# RS485.net
KiCad netlist of a schematic drawn in Altium Designer
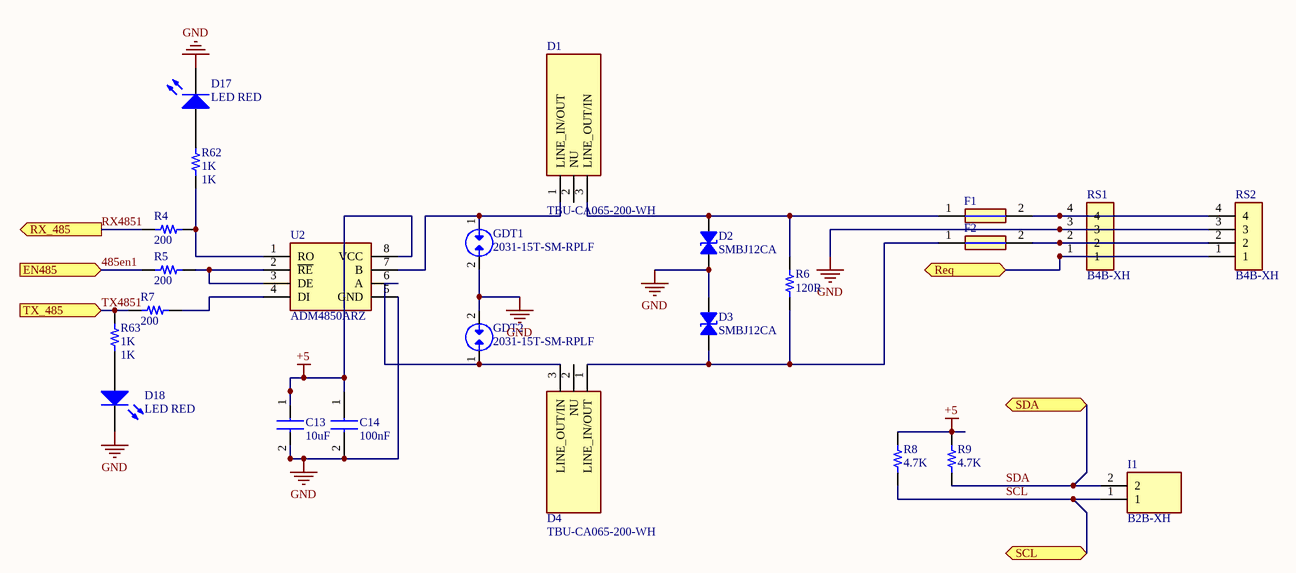
[diagram p0: RS485.SchDoc]

(export (version "E")
  (design (tool "Eeschema 10.0.6"))
  (components
    (comp (ref "C13")
      (value "10uF")
      (footprint "0603C")
      (description "CAP SMD 0603")
      (fields
        (field (name "MANUFACTURER_PART_NUMBER") "C1206C104Z5UACTU")
        (field (name "MOUSER PART NUMBER") "80-C1206C104Z5U")
      )
      (libsource (lib "*") (part "C1206C104Z5UACTU"))
    )
    (comp (ref "C14")
      (value "100nF")
      (footprint "0603C")
      (description "CAP SMD 0603")
      (fields
        (field (name "MANUFACTURER_PART_NUMBER") "C1206C104Z5UACTU")
        (field (name "MOUSER PART NUMBER") "80-C1206C104Z5U")
      )
      (libsource (lib "*") (part "C1206C104Z5UACTU"))
    )
    (comp (ref "D1")
      (value "TBU-CA065-200-WH")
      (footprint "TBUCA025050WH")
      (description "TVS Diode (Bi-directional)")
      (fields (field (name "MOUSER PART NUMBER") "652-TBU-CA065-200-WH"))
      (libsource (lib "*") (part "TBU-CA065-200-WH"))
    )
    (comp (ref "D2")
      (value "SMBJ12CA")
      (footprint "DO214AA SMB")
      (description "TVS DIODE 12V 19.9V SMB")
      (fields (field (name "MANUFACTURER") "AVX Corporation"))
      (libsource (lib "Celestial Altium Library - altium_library") (part "Diode TVS"))
    )
    (comp (ref "D3")
      (value "SMBJ12CA")
      (footprint "DO214AA SMB")
      (description "TVS DIODE 12V 19.9V SMB")
      (fields (field (name "MANUFACTURER") "AVX Corporation"))
      (libsource (lib "Celestial Altium Library - altium_library") (part "Diode TVS"))
    )
    (comp (ref "D4")
      (value "TBU-CA065-200-WH")
      (footprint "TBUCA025050WH")
      (description "TVS Diode (Bi-directional)")
      (fields (field (name "MOUSER PART NUMBER") "652-TBU-CA065-200-WH"))
      (libsource (lib "") (part "TBU-CA065-200-WH_1"))
    )
    (comp (ref "D17")
      (value "LED RED")
      (footprint "LED_0805 G")
      (description "LED SMD 0805 RED")
      (fields (field (name "PUBLISHER") "Altium Limited"))
      (libsource (lib "Miscellaneous Devices") (part "LED0"))
    )
    (comp (ref "D18")
      (value "LED RED")
      (footprint "LED_0805 G")
      (description "LED SMD 0805 RED")
      (fields (field (name "PUBLISHER") "Altium Limited"))
      (libsource (lib "Miscellaneous Devices") (part "LED0"))
    )
    (comp (ref "F1")
      (value "fuse 100mAmp")
      (footprint "1206 FUSE")
      (description "Fuse 1206")
      (fields (field (name "MANUFACTURER_PART_NUMBER") "1206SFS200F/63-2"))
      (libsource (lib "*") (part "1206SFS200F_63-2"))
    )
    (comp (ref "F2")
      (value "fuse 100mAmp")
      (footprint "1206 FUSE")
      (description "Fuse 1206")
      (fields (field (name "MANUFACTURER_PART_NUMBER") "1206SFS200F/63-2"))
      (libsource (lib "*") (part "1206SFS200F_63-2"))
    )
    (comp (ref "GDT1")
      (value "2031-15T-SM-RPLF")
      (footprint "TVS_2031-15T-SM-RPLF")
      (description "Gas Discharge Tube SMD")
      (libsource (lib "2031-15T-SM-RPLF") (part "2031-15T-SM-RPLF"))
    )
    (comp (ref "GDT2")
      (value "2031-15T-SM-RPLF")
      (footprint "TVS_2031-15T-SM-RPLF")
      (description "Gas Discharge Tube SMD")
      (libsource (lib "2031-15T-SM-RPLF") (part "2031-15T-SM-RPLF"))
    )
    (comp (ref "I1")
      (value "B2B-XH")
      (footprint "JST-B2B-XH")
      (description "XH 2pin standing")
      (libsource (lib "XHBBLIB") (part "B2B-XH"))
    )
    (comp (ref "R4")
      (value "200")
      (footprint "0603R")
      (description "RES SMD 0603")
      (fields (field (name "PART NUMBER") "CRCW080510K0JNEAIF") (field (name "MANUFACTURER") "Vishay Dale"))
      (libsource (lib "Celestial Altium Library - altium_library") (part "Resistor"))
    )
    (comp (ref "R5")
      (value "200")
      (footprint "0603R")
      (description "RES SMD 0603")
      (fields (field (name "PART NUMBER") "CRCW080510K0JNEAIF") (field (name "MANUFACTURER") "Vishay Dale"))
      (libsource (lib "Celestial Altium Library - altium_library") (part "Resistor"))
    )
    (comp (ref "R6")
      (value "120R")
      (footprint "0603R")
      (description "RES SMD 0603")
      (fields (field (name "PART NUMBER") "CRCW080510K0JNEAIF") (field (name "MANUFACTURER") "Vishay Dale"))
      (libsource (lib "Celestial Altium Library - altium_library") (part "Resistor"))
    )
    (comp (ref "R7")
      (value "200")
      (footprint "0603R")
      (description "RES SMD 0603")
      (fields (field (name "PART NUMBER") "CRCW080510K0JNEAIF") (field (name "MANUFACTURER") "Vishay Dale"))
      (libsource (lib "Celestial Altium Library - altium_library") (part "Resistor"))
    )
    (comp (ref "R8")
      (value "4.7K")
      (footprint "0603R")
      (description "RES SMD 0603")
      (fields (field (name "PART NUMBER") "CRCW080510K0JNEAIF") (field (name "MANUFACTURER") "Vishay Dale"))
      (libsource (lib "Celestial Altium Library - altium_library") (part "Resistor"))
    )
    (comp (ref "R9")
      (value "4.7K")
      (footprint "0603R")
      (description "RES SMD 0603")
      (fields (field (name "PART NUMBER") "CRCW080510K0JNEAIF") (field (name "MANUFACTURER") "Vishay Dale"))
      (libsource (lib "Celestial Altium Library - altium_library") (part "Resistor"))
    )
    (comp (ref "R62")
      (value "1K")
      (footprint "0603R")
      (description "RES SMD 0603")
      (fields (field (name "PART NUMBER") "RCS0805100KFKEA") (field (name "ALTIUM_VALUE") "1K"))
      (libsource (lib "lamp control-ver2") (part "Resistor"))
    )
    (comp (ref "R63")
      (value "1K")
      (footprint "0603R")
      (description "RES SMD 0603")
      (fields (field (name "PART NUMBER") "RCS0805100KFKEA") (field (name "ALTIUM_VALUE") "1K"))
      (libsource (lib "lamp control-ver2") (part "Resistor"))
    )
    (comp (ref "RS1")
      (value "B4B-XH")
      (footprint "JST-B4B-XH")
      (description "XH 4pin standing")
      (libsource (lib "XHBBLIB") (part "B4B-XH"))
    )
    (comp (ref "RS2")
      (value "B4B-XH")
      (footprint "JST-B4B-XH")
      (description "XH 4pin standing")
      (libsource (lib "XHBBLIB") (part "B4B-XH"))
    )
    (comp (ref "U2")
      (value "ADM4850ARZ")
      (footprint "SO8_N")
      (description "MAX485 SMD")
      (fields (field (name "MOUSER PART NUMBER") "584-ADM4850ARZ"))
      (libsource (lib "*") (part "ADM4850ARZ"))
    )
  )
  (nets
    (net (code "1") (name "+5") (class "Default")
      (node (ref "C13") (pin "1") (pinfunction "1_1") (pintype "passive"))
      (node (ref "C14") (pin "1") (pinfunction "1_1") (pintype "passive"))
      (node (ref "R8") (pin "1") (pinfunction "1_1") (pintype "passive"))
      (node (ref "R9") (pin "1") (pinfunction "1_1") (pintype "passive"))
      (node (ref "U2") (pin "8") (pinfunction "VCC_8") (pintype "passive"))
    )
    (net (code "2") (name "/485en1") (class "Default")
      (node (ref "R5") (pin "2") (pinfunction "2_2") (pintype "passive"))
    )
    (net (code "3") (name "/RX4851") (class "Default")
      (node (ref "R4") (pin "2") (pinfunction "2_2") (pintype "passive"))
    )
    (net (code "4") (name "/Req") (class "Default")
      (node (ref "RS1") (pin "1") (pinfunction "1_1") (pintype "passive"))
      (node (ref "RS2") (pin "1") (pinfunction "1_1") (pintype "passive"))
    )
    (net (code "5") (name "/SCL") (class "Default")
      (node (ref "I1") (pin "1") (pinfunction "1_1") (pintype "passive"))
      (node (ref "R8") (pin "2") (pinfunction "2_2") (pintype "passive"))
    )
    (net (code "6") (name "/SDA") (class "Default")
      (node (ref "I1") (pin "2") (pinfunction "2_2") (pintype "passive"))
      (node (ref "R9") (pin "2") (pinfunction "2_2") (pintype "passive"))
    )
    (net (code "7") (name "/TX4851") (class "Default")
      (node (ref "R63") (pin "2") (pinfunction "2_2") (pintype "passive"))
      (node (ref "R7") (pin "2") (pinfunction "2_2") (pintype "passive"))
    )
    (net (code "8") (name "GND") (class "Default")
      (node (ref "C13") (pin "2") (pinfunction "2_2") (pintype "passive"))
      (node (ref "C14") (pin "2") (pinfunction "2_2") (pintype "passive"))
      (node (ref "D17") (pin "2") (pinfunction "K_2") (pintype "passive"))
      (node (ref "D18") (pin "2") (pinfunction "K_2") (pintype "passive"))
      (node (ref "D2") (pin "1") (pinfunction "1_1") (pintype "passive"))
      (node (ref "D3") (pin "2") (pinfunction "2_2") (pintype "passive"))
      (node (ref "GDT1") (pin "2") (pinfunction "2_2") (pintype "passive"))
      (node (ref "GDT2") (pin "2") (pinfunction "2_2") (pintype "passive"))
      (node (ref "RS1") (pin "3") (pinfunction "3_3") (pintype "passive"))
      (node (ref "RS2") (pin "3") (pinfunction "3_3") (pintype "passive"))
      (node (ref "U2") (pin "5") (pinfunction "GND_5") (pintype "passive"))
    )
    (net (code "9") (name "Net-(D1-LINE_IN{slash}OUT)") (class "Default")
      (node (ref "D1") (pin "1") (pinfunction "LINE_IN/OUT_1") (pintype "passive"))
      (node (ref "GDT1") (pin "1") (pinfunction "1_1") (pintype "passive"))
      (node (ref "U2") (pin "7") (pinfunction "B_7") (pintype "passive"))
    )
    (net (code "10") (name "Net-(D1-LINE_OUT{slash}IN)") (class "Default")
      (node (ref "D1") (pin "3") (pinfunction "LINE_OUT/IN_3") (pintype "passive"))
      (node (ref "D2") (pin "2") (pinfunction "2_2") (pintype "passive"))
      (node (ref "F1") (pin "1") (pinfunction "1_1") (pintype "passive"))
      (node (ref "R6") (pin "1") (pinfunction "1_1") (pintype "passive"))
    )
    (net (code "11") (name "Net-(D4-LINE_IN{slash}OUT)") (class "Default")
      (node (ref "D3") (pin "1") (pinfunction "1_1") (pintype "passive"))
      (node (ref "D4") (pin "1") (pinfunction "LINE_IN/OUT_1") (pintype "passive"))
      (node (ref "F2") (pin "1") (pinfunction "1_1") (pintype "passive"))
      (node (ref "R6") (pin "2") (pinfunction "2_2") (pintype "passive"))
    )
    (net (code "12") (name "Net-(D4-LINE_OUT{slash}IN)") (class "Default")
      (node (ref "D4") (pin "3") (pinfunction "LINE_OUT/IN_3") (pintype "passive"))
      (node (ref "GDT2") (pin "1") (pinfunction "1_1") (pintype "passive"))
      (node (ref "U2") (pin "6") (pinfunction "A_6") (pintype "passive"))
    )
    (net (code "13") (name "Net-(D17-A)") (class "Default")
      (node (ref "D17") (pin "1") (pinfunction "A_1") (pintype "passive"))
      (node (ref "R62") (pin "1") (pinfunction "1_1") (pintype "passive"))
    )
    (net (code "14") (name "Net-(D18-A)") (class "Default")
      (node (ref "D18") (pin "1") (pinfunction "A_1") (pintype "passive"))
      (node (ref "R63") (pin "1") (pinfunction "1_1") (pintype "passive"))
    )
    (net (code "15") (name "Net-(F1-Pad2)") (class "Default")
      (node (ref "F1") (pin "2") (pinfunction "2_2") (pintype "passive"))
      (node (ref "RS1") (pin "4") (pinfunction "4_4") (pintype "passive"))
      (node (ref "RS2") (pin "4") (pinfunction "4_4") (pintype "passive"))
    )
    (net (code "16") (name "Net-(F2-Pad2)") (class "Default")
      (node (ref "F2") (pin "2") (pinfunction "2_2") (pintype "passive"))
      (node (ref "RS1") (pin "2") (pinfunction "2_2") (pintype "passive"))
      (node (ref "RS2") (pin "2") (pinfunction "2_2") (pintype "passive"))
    )
    (net (code "17") (name "Net-(U2-DE)") (class "Default")
      (node (ref "R5") (pin "1") (pinfunction "1_1") (pintype "passive"))
      (node (ref "U2") (pin "2") (pinfunction "~{RE}_2") (pintype "passive"))
      (node (ref "U2") (pin "3") (pinfunction "DE_3") (pintype "passive"))
    )
    (net (code "18") (name "Net-(U2-DI)") (class "Default")
      (node (ref "R7") (pin "1") (pinfunction "1_1") (pintype "passive"))
      (node (ref "U2") (pin "4") (pinfunction "DI_4") (pintype "passive"))
    )
    (net (code "19") (name "Net-(U2-RO)") (class "Default")
      (node (ref "R4") (pin "1") (pinfunction "1_1") (pintype "passive"))
      (node (ref "R62") (pin "2") (pinfunction "2_2") (pintype "passive"))
      (node (ref "U2") (pin "1") (pinfunction "RO_1") (pintype "passive"))
    )
    (net (code "20") (name "unconnected-(D1-NU-Pad2)") (class "Default")
      (node (ref "D1") (pin "2") (pinfunction "NU_2") (pintype "passive"))
    )
    (net (code "21") (name "unconnected-(D4-NU-Pad2)") (class "Default")
      (node (ref "D4") (pin "2") (pinfunction "NU_2") (pintype "passive"))
    )
  )
)
